# OR_GATE.net
KiCad netlist of a schematic drawn in EAGLE
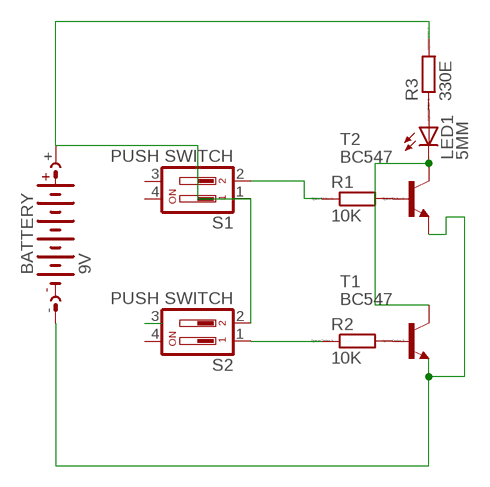
[diagram p0: schematic, sheet 1]

(export (version "E")
  (design (tool "Eeschema 10.0.6"))
  (components
    (comp (ref "BATTERY")
      (value "9V")
      (footprint "eagle-import:AB9V")
      (libsource (lib "eagle-import") (part "AB9V"))
    )
    (comp (ref "LED1")
      (value "5MM")
      (footprint "eagle-import:LED5MM")
      (libsource (lib "eagle-import") (part "LED5MM"))
    )
    (comp (ref "R1")
      (value "10K")
      (footprint "eagle-import:0204_7")
      (libsource (lib "eagle-import") (part "R0204/7"))
    )
    (comp (ref "R2")
      (value "10K")
      (footprint "eagle-import:0204_7")
      (libsource (lib "eagle-import") (part "R0204/7"))
    )
    (comp (ref "R3")
      (value "330E")
      (footprint "eagle-import:0204_7")
      (libsource (lib "eagle-import") (part "R0204/7"))
    )
    (comp (ref "S1")
      (value "PUSH SWITCH")
      (footprint "eagle-import:DS-02")
      (libsource (lib "eagle-import") (part "DS02"))
    )
    (comp (ref "S2")
      (value "PUSH SWITCH")
      (footprint "eagle-import:DS-02")
      (libsource (lib "eagle-import") (part "DS02"))
    )
    (comp (ref "T1")
      (value "BC547")
      (footprint "eagle-import:TO92")
      (libsource (lib "eagle-import") (part "BC547"))
    )
    (comp (ref "T2")
      (value "BC547")
      (footprint "eagle-import:TO92")
      (libsource (lib "eagle-import") (part "BC547"))
    )
  )
  (nets
    (net (code "1") (name "Net-(BATTERY-Pad+)") (class "Default")
      (node (ref "BATTERY") (pin "+") (pinfunction "+_+") (pintype "passive"))
      (node (ref "R3") (pin "2") (pinfunction "2_2") (pintype "passive"))
      (node (ref "S1") (pin "1") (pinfunction "1_1") (pintype "passive"))
      (node (ref "S2") (pin "2") (pinfunction "2_2") (pintype "passive"))
    )
    (net (code "2") (name "Net-(LED1-C)") (class "Default")
      (node (ref "LED1") (pin "K") (pinfunction "C_K") (pintype "passive"))
      (node (ref "T1") (pin "3") (pinfunction "C_3") (pintype "passive"))
      (node (ref "T2") (pin "3") (pinfunction "C_3") (pintype "passive"))
    )
    (net (code "3") (name "Net-(LED1-PadA)") (class "Default")
      (node (ref "LED1") (pin "A") (pinfunction "A_A") (pintype "passive"))
      (node (ref "R3") (pin "1") (pinfunction "1_1") (pintype "passive"))
    )
    (net (code "4") (name "Net-(R1-Pad1)") (class "Default")
      (node (ref "R1") (pin "1") (pinfunction "1_1") (pintype "passive"))
      (node (ref "S1") (pin "2") (pinfunction "2_2") (pintype "passive"))
    )
    (net (code "5") (name "Net-(R2-Pad1)") (class "Default")
      (node (ref "R2") (pin "1") (pinfunction "1_1") (pintype "passive"))
      (node (ref "S2") (pin "1") (pinfunction "1_1") (pintype "passive"))
    )
    (net (code "6") (name "Net-(T1-B)") (class "Default")
      (node (ref "R2") (pin "2") (pinfunction "2_2") (pintype "passive"))
      (node (ref "T1") (pin "2") (pinfunction "B_2") (pintype "passive"))
    )
    (net (code "7") (name "Net-(T1-E)") (class "Default")
      (node (ref "BATTERY") (pin "-") (pinfunction "-_-") (pintype "passive"))
      (node (ref "T1") (pin "1") (pinfunction "E_1") (pintype "passive"))
      (node (ref "T2") (pin "1") (pinfunction "E_1") (pintype "passive"))
    )
    (net (code "8") (name "Net-(T2-B)") (class "Default")
      (node (ref "R1") (pin "2") (pinfunction "2_2") (pintype "passive"))
      (node (ref "T2") (pin "2") (pinfunction "B_2") (pintype "passive"))
    )
    (net (code "9") (name "unconnected-(S1-Pad3)") (class "Default")
      (node (ref "S1") (pin "3") (pinfunction "3_3") (pintype "passive"))
    )
    (net (code "10") (name "unconnected-(S1-Pad4)") (class "Default")
      (node (ref "S1") (pin "4") (pinfunction "4_4") (pintype "passive"))
    )
    (net (code "11") (name "unconnected-(S2-Pad3)") (class "Default")
      (node (ref "S2") (pin "3") (pinfunction "3_3") (pintype "passive"))
    )
    (net (code "12") (name "unconnected-(S2-Pad4)") (class "Default")
      (node (ref "S2") (pin "4") (pinfunction "4_4") (pintype "passive"))
    )
  )
)
